# TempSense.net
KiCad netlist of a schematic drawn in Altium Designer
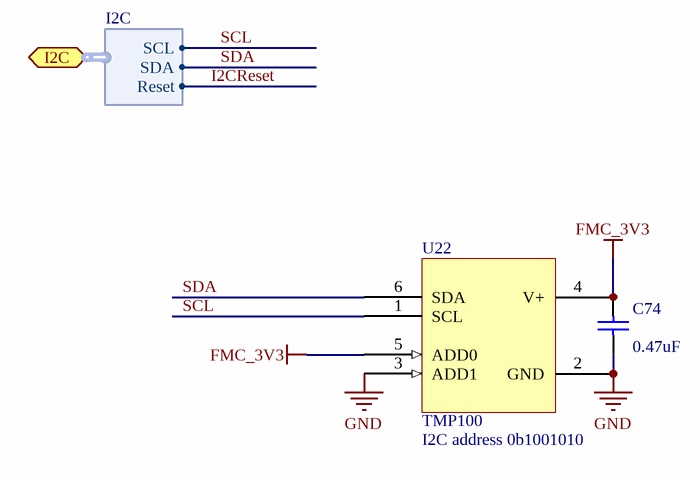
[diagram p0: TempSense.SchDoc]

(export (version "E")
  (design (tool "Eeschema 10.0.6"))
  (components
    (comp (ref "C74")
      (value "0.47uF")
      (footprint "0402")
      (description "Capacitor (Semiconductor SIM Model)")
      (fields (field (name "MANUFACTURER") "e.g Taiyo Yuden"))
      (libsource (lib "gsmecher") (part "Cap Semi"))
    )
    (comp (ref "U22")
      (value "TMP100")
      (footprint "SOT23-6")
      (description "Digital Temperature Sensor with I2C Interface")
      (fields (field (name "MANUFACTURER") "Texas Instruments"))
      (libsource (lib "MGMEZZ04") (part "TMP100"))
    )
  )
  (nets
    (net (code "3") (name "/SCL") (class "Default")
      (node (ref "U22") (pin "1") (pinfunction "SCL_1") (pintype "open_collector"))
    )
    (net (code "4") (name "/SDA") (class "Default")
      (node (ref "U22") (pin "6") (pinfunction "SDA_6") (pintype "open_collector"))
    )
    (net (code "6") (name "FMC_3V3") (class "Default")
      (node (ref "C74") (pin "2") (pinfunction "2_2") (pintype "passive"))
      (node (ref "U22") (pin "4") (pinfunction "V+_4") (pintype "power_in"))
      (node (ref "U22") (pin "5") (pinfunction "ADD0_5") (pintype "input"))
    )
    (net (code "7") (name "GND") (class "Default")
      (node (ref "C74") (pin "1") (pinfunction "1_1") (pintype "passive"))
      (node (ref "U22") (pin "2") (pinfunction "GND_2") (pintype "power_in"))
      (node (ref "U22") (pin "3") (pinfunction "ADD1_3") (pintype "input"))
    )
  )
)
